# Power_stage.net
KiCad netlist of a schematic drawn in Altium Designer
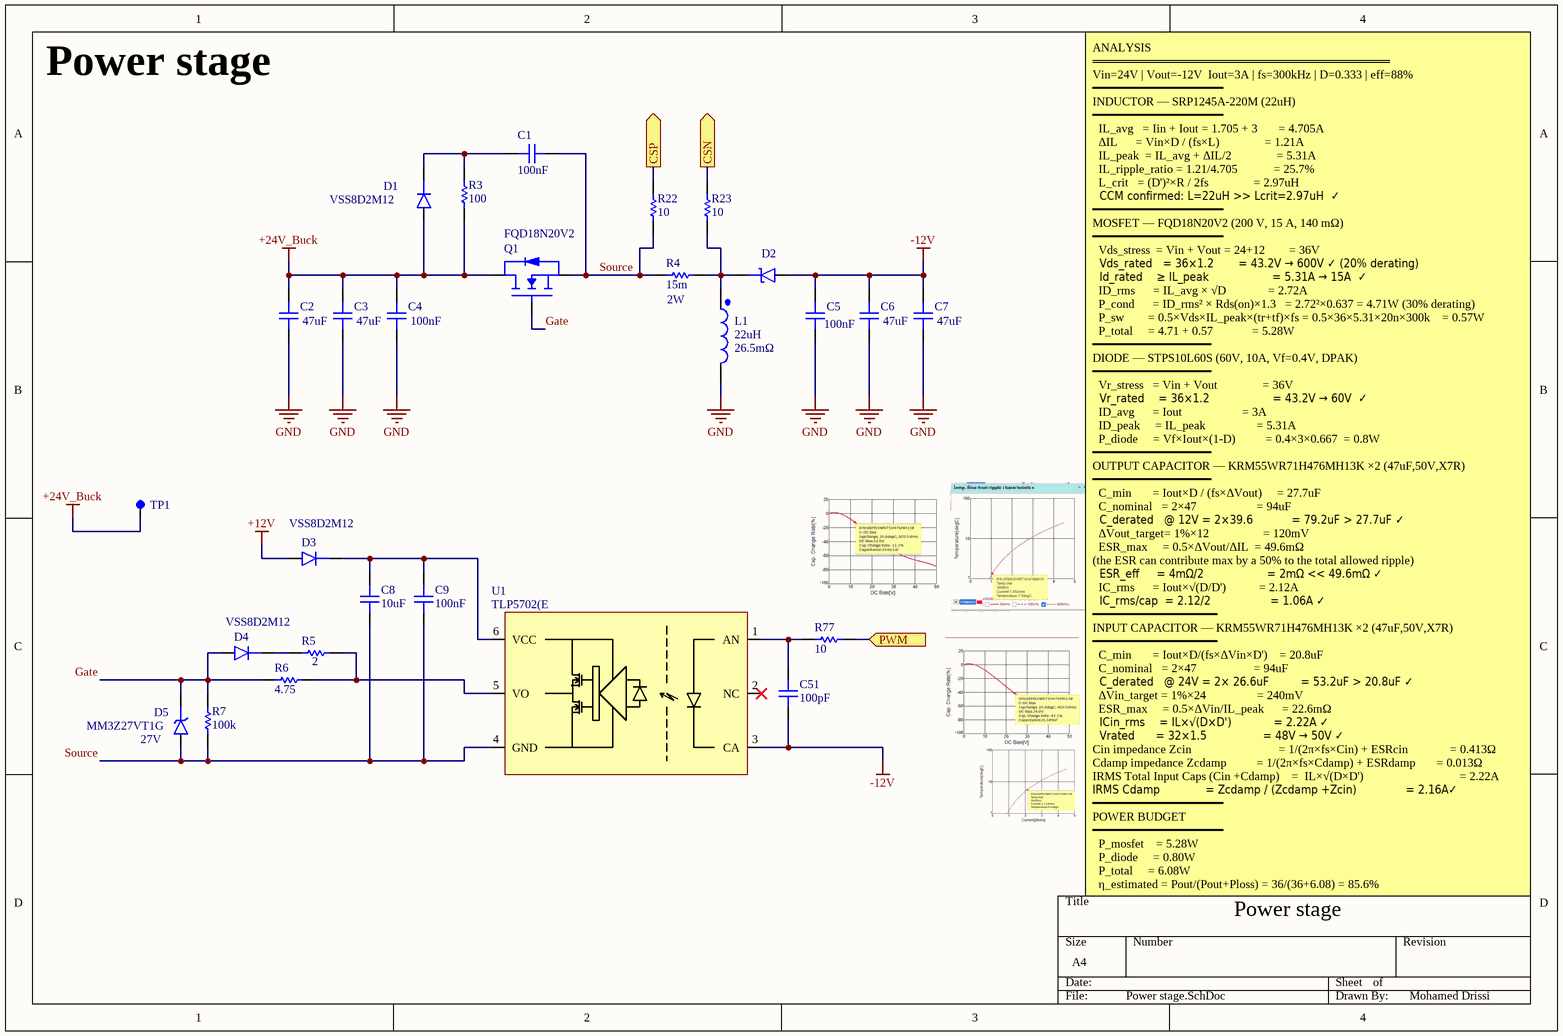
[diagram p0: Power stage.SchDoc]

(export (version "E")
  (design (tool "Eeschema 10.0.6"))
  (components
    (comp (ref "C1")
      (value "GMC10X7R104K100NT")
      (footprint "cap_0603")
      (description "100V 100nF X7R ±10% 0603 Multilayer Ceramic Capacitors MLCC - SMD/SMT ROHS")
      (fields (field (name "MANUFACTURER") "Cal-Chip Electronics") (field (name "CAPACITANCE") "100nF"))
      (libsource (lib "Inverting buck boost") (part "Cal-chip GMC10X7R104K100NT"))
    )
    (comp (ref "C2")
      (value "KRM55WR71H476MH13K")
      (footprint "cap_2220")
      (description "Multilayer Ceramic Capacitors MLCC - SMD/SMT 47uF 50VDC 20% X7R")
      (fields
        (field (name "MANUFACTURER") "Murata")
        (field (name "TOLERANCE") "20%")
        (field (name "CAPACITANCE") "47uF")
      )
      (libsource (lib "Inverting buck boost") (part "Murata KRM55WR71H476MH13K"))
    )
    (comp (ref "C3")
      (value "KRM55WR71H476MH13K")
      (footprint "cap_2220")
      (description "Multilayer Ceramic Capacitors MLCC - SMD/SMT 47uF 50VDC 20% X7R")
      (fields
        (field (name "MANUFACTURER") "Murata")
        (field (name "TOLERANCE") "20%")
        (field (name "CAPACITANCE") "47uF")
      )
      (libsource (lib "Inverting buck boost") (part "Murata KRM55WR71H476MH13K"))
    )
    (comp (ref "C4")
      (value "GMC10X7R104K100NT")
      (footprint "cap_0603")
      (description "100V 100nF X7R ±10% 0603 Multilayer Ceramic Capacitors MLCC - SMD/SMT ROHS")
      (fields (field (name "MANUFACTURER") "Cal-Chip Electronics") (field (name "CAPACITANCE") "100nF"))
      (libsource (lib "Inverting buck boost") (part "Cal-chip GMC10X7R104K100NT"))
    )
    (comp (ref "C5")
      (value "GMC10X7R104K100NT")
      (footprint "cap_0603")
      (description "100V 100nF X7R ±10% 0603 Multilayer Ceramic Capacitors MLCC - SMD/SMT ROHS")
      (fields (field (name "MANUFACTURER") "Cal-Chip Electronics") (field (name "CAPACITANCE") "100nF"))
      (libsource (lib "Inverting buck boost") (part "Cal-chip GMC10X7R104K100NT"))
    )
    (comp (ref "C6")
      (value "KRM55WR71H476MH13K")
      (footprint "cap_2220")
      (description "Multilayer Ceramic Capacitors MLCC - SMD/SMT 47uF 50VDC 20% X7R")
      (fields
        (field (name "MANUFACTURER") "Murata")
        (field (name "TOLERANCE") "20%")
        (field (name "CAPACITANCE") "47uF")
      )
      (libsource (lib "Inverting buck boost") (part "Murata KRM55WR71H476MH13K"))
    )
    (comp (ref "C7")
      (value "KRM55WR71H476MH13K")
      (footprint "cap_2220")
      (description "Multilayer Ceramic Capacitors MLCC - SMD/SMT 47uF 50VDC 20% X7R")
      (fields
        (field (name "MANUFACTURER") "Murata")
        (field (name "TOLERANCE") "20%")
        (field (name "CAPACITANCE") "47uF")
      )
      (libsource (lib "Inverting buck boost") (part "Murata KRM55WR71H476MH13K"))
    )
    (comp (ref "C8")
      (value "885012209073")
      (footprint "cap_1210")
      (description "Cap, 10Uf, 50V, Mlcc, 1210 Rohs Compliant: Yes ¦Würth Elektronik 885012209073")
      (fields
        (field (name "MANUFACTURER") "Wurth Elektronik")
        (field (name "TOLERANCE") "10%")
        (field (name "CAPACITANCE") "10uF")
      )
      (libsource (lib "Inverting buck boost") (part "Wurth 885012209073"))
    )
    (comp (ref "C9")
      (value "GMC10X7R104K100NT")
      (footprint "cap_0603")
      (description "100V 100nF X7R ±10% 0603 Multilayer Ceramic Capacitors MLCC - SMD/SMT ROHS")
      (fields (field (name "MANUFACTURER") "Cal-Chip Electronics") (field (name "CAPACITANCE") "100nF"))
      (libsource (lib "Inverting buck boost") (part "Cal-chip GMC10X7R104K100NT"))
    )
    (comp (ref "C51")
      (value "GCM1885C2A101JA16D")
      (footprint "Cap_0603")
      (description "100V 100pF C0G ±5% 0603 Multilayer Ceramic Capacitors MLCC - SMD/SMT ROHS")
      (fields
        (field (name "MANUFACTURER") "Murata")
        (field (name "TOLERANCE") "5%")
        (field (name "CAPACITANCE") "100pF")
      )
      (libsource (lib "Inverting buck boost") (part "Murata GCM1885C2A101JA16D"))
    )
    (comp (ref "D1")
      (value "VSS8D2M12")
      (footprint "DO-221AD")
      (description "Rectifier Diode, Schottky, 1 Phase, 1 Element, 2A, 120V V(RRM), Silicon, DO-221AD")
      (fields
        (field (name "MANUFACTURER") "Vishay")
        (field (name "MANUFACTURER PART NUMBER") "VSS8D2M12-M3/H")
      )
      (libsource (lib "Inverting buck boost") (part "Vishay VSS8D2M12-M3/H"))
    )
    (comp (ref "D2")
      (value "STPS10L60D")
      (footprint "TO-220")
      (description "Rectifier Diode, Schottky, 1 Phase, 1 Element, 10A, 60V V(RRM), Silicon, TO-220AC")
      (fields (field (name "MANUFACTURER") "STMicroelectronics"))
      (libsource (lib "Inverting buck boost") (part "ST STPS10L60D"))
    )
    (comp (ref "D3")
      (value "VSS8D2M12")
      (footprint "DO-221AD")
      (description "Rectifier Diode, Schottky, 1 Phase, 1 Element, 2A, 120V V(RRM), Silicon, DO-221AD")
      (fields
        (field (name "MANUFACTURER") "Vishay")
        (field (name "MANUFACTURER PART NUMBER") "VSS8D2M12-M3/H")
      )
      (libsource (lib "Inverting buck boost") (part "Vishay VSS8D2M12-M3/H"))
    )
    (comp (ref "D4")
      (value "VSS8D2M12")
      (footprint "DO-221AD")
      (description "Rectifier Diode, Schottky, 1 Phase, 1 Element, 2A, 120V V(RRM), Silicon, DO-221AD")
      (fields
        (field (name "MANUFACTURER") "Vishay")
        (field (name "MANUFACTURER PART NUMBER") "VSS8D2M12-M3/H")
      )
      (libsource (lib "Inverting buck boost") (part "Vishay VSS8D2M12-M3/H"))
    )
    (comp (ref "D5")
      (value "MM3Z27VT1G")
      (footprint "SOD-323")
      (description "Diode, Zener, Vr 27V, If 10MA, Pkg SOD-323, Vf 0.9V, Cj 70PF, Tj +150C, Pd 200MW, Ir 2MA")
      (fields
        (field (name "MANUFACTURER") "onsemi")
        (field (name "TOLERANCE") "7%")
        (field (name "REFERENCE VOLTAGE") "27V")
      )
      (libsource (lib "Inverting buck boost") (part "Onsemi MM3Z27VT1G"))
    )
    (comp (ref "L1")
      (value "MWLA1707S-220MT")
      (footprint "MWLA1707S")
      (description "General Purpose Inductor, 22uH, 20%, 1 Element, Wirewound-Core, SMD, 6967")
      (fields
        (field (name "MANUFACTURER") "Sunlord")
        (field (name "TOLERANCE") "20%")
        (field (name "DC RESISTANCE (DCR)") "26.5mΩ")
        (field (name "INDUCTANCE") "22uH")
      )
      (libsource (lib "Inverting buck boost") (part "Shenzen MWLA1707S-220MT"))
    )
    (comp (ref "Q1")
      (value "FQD18N20V2")
      (footprint "TO-252  (DPAK)")
      (description "N-Channel Power MOSFET, QFET®, 200 V, 15 A, 140 mΩ, DPAK")
      (fields (field (name "MANUFACTURER") "onsemi") (field (name "MANUFACTURER PART NUMBER") "FQD18N20V2TM"))
      (libsource (lib "Inverting buck boost") (part "Onsemi FQD18N20V2TM"))
    )
    (comp (ref "R3")
      (value "CPA2512E1000FS-T10")
      (footprint "res_2512")
      (fields
        (field (name "MANUFACTURER") "Susumu")
        (field (name "TOLERANCE") "1%")
        (field (name "RESISTANCE") "100")
      )
      (libsource (lib "Inverting buck boost") (part "Susumu CPA2512E1000FS-T10"))
    )
    (comp (ref "R4")
      (value "D1MPAB2512QR015FA-T4")
      (footprint "res_2512")
      (description "Res 0.015 Ohm 1% 2W 2512")
      (fields
        (field (name "MANUFACTURER") "Thin Film Tech")
        (field (name "RESISTANCE") "15m")
        (field (name "POWER") "2W")
      )
      (libsource (lib "Inverting buck boost") (part "Thin Film D1MPAB2512QR015FA-T4"))
    )
    (comp (ref "R5")
      (value "2")
      (footprint "res_0603")
      (description "Res Thick Film 0603 2 Ohm 1% 0.1W(1/10W) ±100ppm/C Pad SMD T/R Automotive AEC-Q200")
      (fields
        (field (name "MANUFACTURER") "Vishay")
        (field (name "MANUFACTURER PART NUMBER") "CRCW06032R00FKEA")
      )
      (libsource (lib "Inverting buck boost") (part "Vishay CRCW06032R00FKEA"))
    )
    (comp (ref "R6")
      (value "4.75")
      (footprint "res_0603")
      (fields
        (field (name "MANUFACTURER") "Vishay")
        (field (name "MANUFACTURER PART NUMBER") "CRCW06034R75FKEAHP")
        (field (name "TOLERANCE") "1%")
      )
      (libsource (lib "Inverting buck boost") (part "Vishay CRCW06034R75FKEAHP"))
    )
    (comp (ref "R7")
      (value "CRCW0603100KFKEA")
      (footprint "res_0603")
      (description "Res Thick Film 0603 100K Ohm 1% 1/3W ±100ppm/°C Molded SMD SMD Paper T/R")
      (fields
        (field (name "MANUFACTURER") "Vishay")
        (field (name "MANUFACTURER PART NUMBER") "CRCW0603100KFKEAHP")
        (field (name "RESISTANCE") "100k")
      )
      (libsource (lib "Inverting buck boost") (part "Vishay CRCW0603100KFKEAHP"))
    )
    (comp (ref "R22")
      (value "RC0603FR-0710RL")
      (footprint "res_0603")
      (description "Res Thick Film 0603 1K Ohm 1% 0.1W(1/10W) ±100ppm/°C Pad SMD T/R / RES SMD 1K OHM 1% 1/10W 0603")
      (fields
        (field (name "RESISTANCE") "10")
        (field (name "MANUFACTURER") "Yageo Group")
        (field (name "MANUFACTURER PART NUMBER") "RC0603FR-071KL")
      )
      (libsource (lib "Inverting buck boost") (part "Yageo RC0603FR-0710RL"))
    )
    (comp (ref "R23")
      (value "RC0603FR-0710RL")
      (footprint "res_0603")
      (description "Res Thick Film 0603 1K Ohm 1% 0.1W(1/10W) ±100ppm/°C Pad SMD T/R / RES SMD 1K OHM 1% 1/10W 0603")
      (fields
        (field (name "RESISTANCE") "10")
        (field (name "MANUFACTURER") "Yageo Group")
        (field (name "MANUFACTURER PART NUMBER") "RC0603FR-071KL")
      )
      (libsource (lib "Inverting buck boost") (part "Yageo RC0603FR-0710RL"))
    )
    (comp (ref "R77")
      (value "RT0603BRE0710RL")
      (footprint "res_0603")
      (description "Fixed Resistor, Thin Film, 0.1W, 10ohm, 75V, 0.1% +/-Tol, 50ppm/Cel, Surface Mount, 0603")
      (fields
        (field (name "MANUFACTURER") "Yageo Group")
        (field (name "TOLERANCE") "0.1%")
        (field (name "RESISITANCE") "10")
      )
      (libsource (lib "Inverting buck boost") (part "Yageo RT0603BRE0710RL"))
    )
    (comp (ref "TP1")
      (value "5000")
      (footprint "TH TP")
      (description "Cable Wrap, 1/2 Inch, Polyethylene, Natural, 50 Ft, Spirap Series ¦ TE Connectivity 500002-1")
      (fields (field (name "MANUFACTURER") "Keystone"))
      (libsource (lib "Inverting buck boost") (part "Keystone 5000"))
    )
    (comp (ref "U1")
      (value "TLP5702(E")
      (footprint "TOSHIBA: 11-4N1A")
      (description "Optocoupler DC-IN Single Totem-Pole-OUT 6-Pin SOIC Magazine")
      (fields (field (name "MANUFACTURER") "Toshiba"))
      (libsource (lib "Inverting buck boost") (part "Toshiba TLP5702(E"))
    )
  )
  (nets
    (net (code "1") (name "+12V") (class "Default")
      (node (ref "D3") (pin "A") (pinfunction "A_A") (pintype "passive"))
    )
    (net (code "2") (name "+24V_Buck") (class "Default")
      (node (ref "C2") (pin "2") (pinfunction "2_2") (pintype "passive"))
      (node (ref "C3") (pin "2") (pinfunction "2_2") (pintype "passive"))
      (node (ref "C4") (pin "2") (pinfunction "2_2") (pintype "passive"))
      (node (ref "D1") (pin "A") (pinfunction "A_A") (pintype "passive"))
      (node (ref "Q1") (pin "2") (pinfunction "D_2") (pintype "passive"))
      (node (ref "R3") (pin "1") (pinfunction "1_1") (pintype "passive"))
      (node (ref "TP1") (pin "1") (pinfunction "1_1") (pintype "passive"))
    )
    (net (code "3") (name "-12V") (class "Default")
      (node (ref "C5") (pin "2") (pinfunction "2_2") (pintype "passive"))
      (node (ref "C51") (pin "1") (pinfunction "1_1") (pintype "passive"))
      (node (ref "C6") (pin "2") (pinfunction "2_2") (pintype "passive"))
      (node (ref "C7") (pin "2") (pinfunction "2_2") (pintype "passive"))
      (node (ref "D2") (pin "2") (pinfunction "A_2") (pintype "passive"))
      (node (ref "U1") (pin "3") (pinfunction "CA_3") (pintype "passive"))
    )
    (net (code "4") (name "/CSN") (class "Default")
      (node (ref "R23") (pin "2") (pinfunction "2_2") (pintype "passive"))
    )
    (net (code "5") (name "/CSP") (class "Default")
      (node (ref "R22") (pin "2") (pinfunction "2_2") (pintype "passive"))
    )
    (net (code "6") (name "/Gate") (class "Default")
      (node (ref "D4") (pin "A") (pinfunction "A_A") (pintype "passive"))
      (node (ref "D5") (pin "k") (pinfunction "C_k") (pintype "passive"))
      (node (ref "Q1") (pin "1") (pinfunction "G_1") (pintype "passive"))
      (node (ref "R6") (pin "1") (pinfunction "1_1") (pintype "passive"))
      (node (ref "R7") (pin "2") (pinfunction "2_2") (pintype "passive"))
    )
    (net (code "7") (name "/PWM") (class "Default")
      (node (ref "R77") (pin "2") (pinfunction "2_2") (pintype "passive"))
    )
    (net (code "8") (name "/Source") (class "Default")
      (node (ref "C1") (pin "1") (pinfunction "1_1") (pintype "passive"))
      (node (ref "C8") (pin "1") (pinfunction "1_1") (pintype "passive"))
      (node (ref "C9") (pin "1") (pinfunction "1_1") (pintype "passive"))
      (node (ref "D5") (pin "A") (pinfunction "A_A") (pintype "passive"))
      (node (ref "Q1") (pin "3") (pinfunction "S_3") (pintype "passive"))
      (node (ref "R22") (pin "1") (pinfunction "1_1") (pintype "passive"))
      (node (ref "R4") (pin "1") (pinfunction "1_1") (pintype "passive"))
      (node (ref "R7") (pin "1") (pinfunction "1_1") (pintype "passive"))
      (node (ref "U1") (pin "4") (pinfunction "GND_4") (pintype "passive"))
    )
    (net (code "9") (name "GND") (class "Default")
      (node (ref "C2") (pin "1") (pinfunction "1_1") (pintype "passive"))
      (node (ref "C3") (pin "1") (pinfunction "1_1") (pintype "passive"))
      (node (ref "C4") (pin "1") (pinfunction "1_1") (pintype "passive"))
      (node (ref "C5") (pin "1") (pinfunction "1_1") (pintype "passive"))
      (node (ref "C6") (pin "1") (pinfunction "1_1") (pintype "passive"))
      (node (ref "C7") (pin "1") (pinfunction "1_1") (pintype "passive"))
      (node (ref "L1") (pin "2") (pinfunction "2_2") (pintype "passive"))
    )
    (net (code "10") (name "Net-(C1-Pad2)") (class "Default")
      (node (ref "C1") (pin "2") (pinfunction "2_2") (pintype "passive"))
      (node (ref "D1") (pin "C") (pinfunction "C_C") (pintype "passive"))
      (node (ref "R3") (pin "2") (pinfunction "2_2") (pintype "passive"))
    )
    (net (code "11") (name "Net-(D2-K)") (class "Default")
      (node (ref "D2") (pin "1") (pinfunction "K_1") (pintype "passive"))
      (node (ref "L1") (pin "1") (pinfunction "1_1") (pintype "passive"))
      (node (ref "R23") (pin "1") (pinfunction "1_1") (pintype "passive"))
      (node (ref "R4") (pin "2") (pinfunction "2_2") (pintype "passive"))
    )
    (net (code "12") (name "Net-(D4-PadC)") (class "Default")
      (node (ref "D4") (pin "C") (pinfunction "C_C") (pintype "passive"))
      (node (ref "R5") (pin "1") (pinfunction "1_1") (pintype "passive"))
    )
    (net (code "13") (name "Net-(U1-AN)") (class "Default")
      (node (ref "C51") (pin "2") (pinfunction "2_2") (pintype "passive"))
      (node (ref "R77") (pin "1") (pinfunction "1_1") (pintype "passive"))
      (node (ref "U1") (pin "1") (pinfunction "AN_1") (pintype "passive"))
    )
    (net (code "14") (name "Net-(U1-VCC)") (class "Default")
      (node (ref "C8") (pin "2") (pinfunction "2_2") (pintype "passive"))
      (node (ref "C9") (pin "2") (pinfunction "2_2") (pintype "passive"))
      (node (ref "D3") (pin "C") (pinfunction "C_C") (pintype "passive"))
      (node (ref "U1") (pin "6") (pinfunction "VCC_6") (pintype "power_in"))
    )
    (net (code "15") (name "Net-(U1-VO)") (class "Default")
      (node (ref "R5") (pin "2") (pinfunction "2_2") (pintype "passive"))
      (node (ref "R6") (pin "2") (pinfunction "2_2") (pintype "passive"))
      (node (ref "U1") (pin "5") (pinfunction "VO_5") (pintype "open_collector"))
    )
    (net (code "16") (name "unconnected-(U1-NC-Pad2)") (class "Default")
      (node (ref "U1") (pin "2") (pinfunction "NC_2") (pintype "passive+no_connect"))
    )
  )
)
